# Servo12Controller.net
KiCad netlist of a schematic drawn in EAGLE
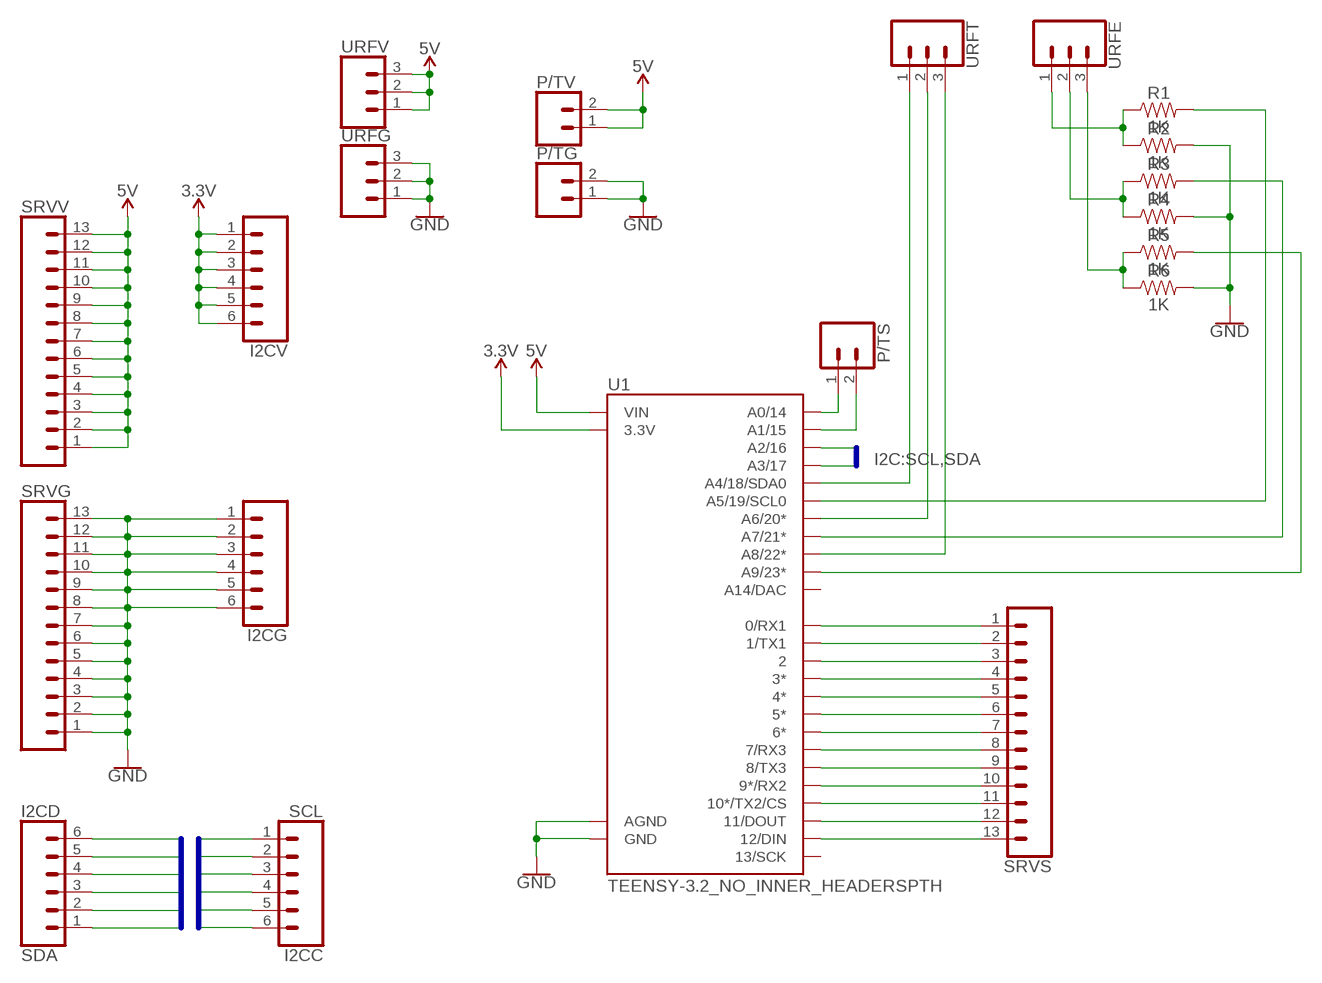
[diagram p0: schematic, sheet 1]

(export (version "E")
  (design (tool "Eeschema 10.0.6"))
  (components
    (comp (ref "I2CC")
      (value "SCL")
      (footprint "eagle-import:1X06_LOCK")
      (libsource (lib "eagle-import") (part "CONN_06LOCK"))
    )
    (comp (ref "I2CD")
      (value "SDA")
      (footprint "eagle-import:1X06_LOCK")
      (libsource (lib "eagle-import") (part "CONN_06LOCK"))
    )
    (comp (ref "I2CG")
      (value "CONN_06LOCK")
      (footprint "eagle-import:1X06_LOCK")
      (libsource (lib "eagle-import") (part "CONN_06LOCK"))
    )
    (comp (ref "I2CV")
      (value "CONN_06LOCK")
      (footprint "eagle-import:1X06_LOCK")
      (libsource (lib "eagle-import") (part "CONN_06LOCK"))
    )
    (comp (ref "P/TG")
      (value "CONN_02LOCK")
      (footprint "eagle-import:1X02_LOCK")
      (libsource (lib "eagle-import") (part "CONN_02LOCK"))
    )
    (comp (ref "P/TS")
      (value "CONN_02LOCK")
      (footprint "eagle-import:1X02_LOCK")
      (libsource (lib "eagle-import") (part "CONN_02LOCK"))
    )
    (comp (ref "P/TV")
      (value "CONN_02LOCK")
      (footprint "eagle-import:1X02_LOCK")
      (libsource (lib "eagle-import") (part "CONN_02LOCK"))
    )
    (comp (ref "R1")
      (value "1K")
      (footprint "eagle-import:AXIAL-0.3")
      (libsource (lib "eagle-import") (part "RESISTORAXIAL-0.3"))
    )
    (comp (ref "R2")
      (value "1K")
      (footprint "eagle-import:AXIAL-0.3")
      (libsource (lib "eagle-import") (part "RESISTORAXIAL-0.3"))
    )
    (comp (ref "R3")
      (value "1K")
      (footprint "eagle-import:AXIAL-0.3")
      (libsource (lib "eagle-import") (part "RESISTORAXIAL-0.3"))
    )
    (comp (ref "R4")
      (value "1K")
      (footprint "eagle-import:AXIAL-0.3")
      (libsource (lib "eagle-import") (part "RESISTORAXIAL-0.3"))
    )
    (comp (ref "R5")
      (value "1K")
      (footprint "eagle-import:AXIAL-0.3")
      (libsource (lib "eagle-import") (part "RESISTORAXIAL-0.3"))
    )
    (comp (ref "R6")
      (value "1K")
      (footprint "eagle-import:AXIAL-0.3")
      (libsource (lib "eagle-import") (part "RESISTORAXIAL-0.3"))
    )
    (comp (ref "SRVG")
      (value "CONN_13LOCK")
      (footprint "eagle-import:1X13_LOCK")
      (libsource (lib "eagle-import") (part "CONN_13LOCK"))
    )
    (comp (ref "SRVS")
      (value "CONN_13LOCK")
      (footprint "eagle-import:1X13_LOCK")
      (libsource (lib "eagle-import") (part "CONN_13LOCK"))
    )
    (comp (ref "SRVV")
      (value "CONN_13LOCK")
      (footprint "eagle-import:1X13_LOCK")
      (libsource (lib "eagle-import") (part "CONN_13LOCK"))
    )
    (comp (ref "U1")
      (value "TEENSY-3.2_NO_INNER_HEADERSPTH")
      (footprint "eagle-import:TEENSY_TEENSY-3.2-PTH")
      (libsource (lib "eagle-import") (part "TEENSY-3.2_NO_INNER_HEADERSPTH"))
    )
    (comp (ref "URFE")
      (value "CONN_03LOCK")
      (footprint "eagle-import:1X03_LOCK")
      (libsource (lib "eagle-import") (part "CONN_03LOCK"))
    )
    (comp (ref "URFG")
      (value "CONN_03LOCK")
      (footprint "eagle-import:1X03_LOCK")
      (libsource (lib "eagle-import") (part "CONN_03LOCK"))
    )
    (comp (ref "URFT")
      (value "CONN_03LOCK")
      (footprint "eagle-import:1X03_LOCK")
      (libsource (lib "eagle-import") (part "CONN_03LOCK"))
    )
    (comp (ref "URFV")
      (value "CONN_03LOCK")
      (footprint "eagle-import:1X03_LOCK")
      (libsource (lib "eagle-import") (part "CONN_03LOCK"))
    )
  )
  (nets
    (net (code "2") (name "/I2C:SCL") (class "Default")
      (node (ref "I2CC") (pin "1") (pinfunction "1_1") (pintype "passive"))
      (node (ref "I2CC") (pin "2") (pinfunction "2_2") (pintype "passive"))
      (node (ref "I2CC") (pin "3") (pinfunction "3_3") (pintype "passive"))
      (node (ref "I2CC") (pin "4") (pinfunction "4_4") (pintype "passive"))
      (node (ref "I2CC") (pin "5") (pinfunction "5_5") (pintype "passive"))
      (node (ref "I2CC") (pin "6") (pinfunction "6_6") (pintype "passive"))
      (node (ref "U1") (pin "16") (pinfunction "A2/16_16") (pintype "bidirectional"))
    )
    (net (code "3") (name "/SDA") (class "Default")
      (node (ref "I2CD") (pin "1") (pinfunction "1_1") (pintype "passive"))
      (node (ref "I2CD") (pin "2") (pinfunction "2_2") (pintype "passive"))
      (node (ref "I2CD") (pin "3") (pinfunction "3_3") (pintype "passive"))
      (node (ref "I2CD") (pin "4") (pinfunction "4_4") (pintype "passive"))
      (node (ref "I2CD") (pin "5") (pinfunction "5_5") (pintype "passive"))
      (node (ref "I2CD") (pin "6") (pinfunction "6_6") (pintype "passive"))
      (node (ref "U1") (pin "17") (pinfunction "A3/17_17") (pintype "bidirectional"))
    )
    (net (code "5") (name "3.3V") (class "Default")
      (node (ref "I2CV") (pin "1") (pinfunction "1_1") (pintype "passive"))
      (node (ref "I2CV") (pin "2") (pinfunction "2_2") (pintype "passive"))
      (node (ref "I2CV") (pin "3") (pinfunction "3_3") (pintype "passive"))
      (node (ref "I2CV") (pin "4") (pinfunction "4_4") (pintype "passive"))
      (node (ref "I2CV") (pin "5") (pinfunction "5_5") (pintype "passive"))
      (node (ref "I2CV") (pin "6") (pinfunction "6_6") (pintype "passive"))
      (node (ref "U1") (pin "3.3V") (pinfunction "3.3V_3.3V") (pintype "bidirectional"))
      (node (ref "U1") (pin "3.3V-1") (pinfunction "3.3V_3.3V-1") (pintype "bidirectional"))
    )
    (net (code "6") (name "5V") (class "Default")
      (node (ref "P/TV") (pin "1") (pinfunction "1_1") (pintype "passive"))
      (node (ref "P/TV") (pin "2") (pinfunction "2_2") (pintype "passive"))
      (node (ref "SRVV") (pin "1") (pinfunction "1_1") (pintype "passive"))
      (node (ref "SRVV") (pin "10") (pinfunction "10_10") (pintype "passive"))
      (node (ref "SRVV") (pin "11") (pinfunction "11_11") (pintype "passive"))
      (node (ref "SRVV") (pin "12") (pinfunction "12_12") (pintype "passive"))
      (node (ref "SRVV") (pin "13") (pinfunction "13_13") (pintype "passive"))
      (node (ref "SRVV") (pin "2") (pinfunction "2_2") (pintype "passive"))
      (node (ref "SRVV") (pin "3") (pinfunction "3_3") (pintype "passive"))
      (node (ref "SRVV") (pin "4") (pinfunction "4_4") (pintype "passive"))
      (node (ref "SRVV") (pin "5") (pinfunction "5_5") (pintype "passive"))
      (node (ref "SRVV") (pin "6") (pinfunction "6_6") (pintype "passive"))
      (node (ref "SRVV") (pin "7") (pinfunction "7_7") (pintype "passive"))
      (node (ref "SRVV") (pin "8") (pinfunction "8_8") (pintype "passive"))
      (node (ref "SRVV") (pin "9") (pinfunction "9_9") (pintype "passive"))
      (node (ref "U1") (pin "VIN") (pinfunction "VIN_VIN") (pintype "bidirectional"))
      (node (ref "URFV") (pin "1") (pinfunction "1_1") (pintype "passive"))
      (node (ref "URFV") (pin "2") (pinfunction "2_2") (pintype "passive"))
      (node (ref "URFV") (pin "3") (pinfunction "3_3") (pintype "passive"))
    )
    (net (code "7") (name "GND") (class "Default")
      (node (ref "I2CG") (pin "1") (pinfunction "1_1") (pintype "passive"))
      (node (ref "I2CG") (pin "2") (pinfunction "2_2") (pintype "passive"))
      (node (ref "I2CG") (pin "3") (pinfunction "3_3") (pintype "passive"))
      (node (ref "I2CG") (pin "4") (pinfunction "4_4") (pintype "passive"))
      (node (ref "I2CG") (pin "5") (pinfunction "5_5") (pintype "passive"))
      (node (ref "I2CG") (pin "6") (pinfunction "6_6") (pintype "passive"))
      (node (ref "P/TG") (pin "1") (pinfunction "1_1") (pintype "passive"))
      (node (ref "P/TG") (pin "2") (pinfunction "2_2") (pintype "passive"))
      (node (ref "R2") (pin "P$2") (pinfunction "2_P$2") (pintype "passive"))
      (node (ref "R4") (pin "P$2") (pinfunction "2_P$2") (pintype "passive"))
      (node (ref "R6") (pin "P$2") (pinfunction "2_P$2") (pintype "passive"))
      (node (ref "SRVG") (pin "1") (pinfunction "1_1") (pintype "passive"))
      (node (ref "SRVG") (pin "10") (pinfunction "10_10") (pintype "passive"))
      (node (ref "SRVG") (pin "11") (pinfunction "11_11") (pintype "passive"))
      (node (ref "SRVG") (pin "12") (pinfunction "12_12") (pintype "passive"))
      (node (ref "SRVG") (pin "13") (pinfunction "13_13") (pintype "passive"))
      (node (ref "SRVG") (pin "2") (pinfunction "2_2") (pintype "passive"))
      (node (ref "SRVG") (pin "3") (pinfunction "3_3") (pintype "passive"))
      (node (ref "SRVG") (pin "4") (pinfunction "4_4") (pintype "passive"))
      (node (ref "SRVG") (pin "5") (pinfunction "5_5") (pintype "passive"))
      (node (ref "SRVG") (pin "6") (pinfunction "6_6") (pintype "passive"))
      (node (ref "SRVG") (pin "7") (pinfunction "7_7") (pintype "passive"))
      (node (ref "SRVG") (pin "8") (pinfunction "8_8") (pintype "passive"))
      (node (ref "SRVG") (pin "9") (pinfunction "9_9") (pintype "passive"))
      (node (ref "U1") (pin "AGND") (pinfunction "AGND_AGND") (pintype "bidirectional"))
      (node (ref "U1") (pin "GND") (pinfunction "GND_GND") (pintype "bidirectional"))
      (node (ref "U1") (pin "GND1") (pinfunction "GND_GND1") (pintype "bidirectional"))
      (node (ref "URFG") (pin "1") (pinfunction "1_1") (pintype "passive"))
      (node (ref "URFG") (pin "2") (pinfunction "2_2") (pintype "passive"))
      (node (ref "URFG") (pin "3") (pinfunction "3_3") (pintype "passive"))
    )
    (net (code "8") (name "Net-(R1-1)") (class "Default")
      (node (ref "R1") (pin "P$1") (pinfunction "1_P$1") (pintype "passive"))
      (node (ref "R2") (pin "P$1") (pinfunction "1_P$1") (pintype "passive"))
      (node (ref "URFE") (pin "1") (pinfunction "1_1") (pintype "passive"))
    )
    (net (code "9") (name "Net-(R1-2)") (class "Default")
      (node (ref "R1") (pin "P$2") (pinfunction "2_P$2") (pintype "passive"))
      (node (ref "U1") (pin "19") (pinfunction "A5/19/SCL0_19") (pintype "bidirectional"))
    )
    (net (code "10") (name "Net-(R3-1)") (class "Default")
      (node (ref "R3") (pin "P$1") (pinfunction "1_P$1") (pintype "passive"))
      (node (ref "R4") (pin "P$1") (pinfunction "1_P$1") (pintype "passive"))
      (node (ref "URFE") (pin "2") (pinfunction "2_2") (pintype "passive"))
    )
    (net (code "11") (name "Net-(R3-2)") (class "Default")
      (node (ref "R3") (pin "P$2") (pinfunction "2_P$2") (pintype "passive"))
      (node (ref "U1") (pin "21") (pinfunction "A7/21*_21") (pintype "bidirectional"))
    )
    (net (code "12") (name "Net-(R5-1)") (class "Default")
      (node (ref "R5") (pin "P$1") (pinfunction "1_P$1") (pintype "passive"))
      (node (ref "R6") (pin "P$1") (pinfunction "1_P$1") (pintype "passive"))
      (node (ref "URFE") (pin "3") (pinfunction "3_3") (pintype "passive"))
    )
    (net (code "13") (name "Net-(R5-2)") (class "Default")
      (node (ref "R5") (pin "P$2") (pinfunction "2_P$2") (pintype "passive"))
      (node (ref "U1") (pin "23") (pinfunction "A9/23*_23") (pintype "bidirectional"))
    )
    (net (code "14") (name "Net-(SRVS-Pad3)") (class "Default")
      (node (ref "SRVS") (pin "3") (pinfunction "3_3") (pintype "passive"))
      (node (ref "U1") (pin "2") (pinfunction "2_2") (pintype "bidirectional"))
    )
    (net (code "15") (name "Net-(U1-0{slash}RX1)") (class "Default")
      (node (ref "SRVS") (pin "1") (pinfunction "1_1") (pintype "passive"))
      (node (ref "U1") (pin "0") (pinfunction "0/RX1_0") (pintype "bidirectional"))
    )
    (net (code "16") (name "Net-(U1-1{slash}TX1)") (class "Default")
      (node (ref "SRVS") (pin "2") (pinfunction "2_2") (pintype "passive"))
      (node (ref "U1") (pin "1") (pinfunction "1/TX1_1") (pintype "bidirectional"))
    )
    (net (code "17") (name "Net-(U1-3*)") (class "Default")
      (node (ref "SRVS") (pin "4") (pinfunction "4_4") (pintype "passive"))
      (node (ref "U1") (pin "3") (pinfunction "3*_3") (pintype "bidirectional"))
    )
    (net (code "18") (name "Net-(U1-4*)") (class "Default")
      (node (ref "SRVS") (pin "5") (pinfunction "5_5") (pintype "passive"))
      (node (ref "U1") (pin "4") (pinfunction "4*_4") (pintype "bidirectional"))
    )
    (net (code "19") (name "Net-(U1-5*)") (class "Default")
      (node (ref "SRVS") (pin "6") (pinfunction "6_6") (pintype "passive"))
      (node (ref "U1") (pin "5") (pinfunction "5*_5") (pintype "bidirectional"))
    )
    (net (code "20") (name "Net-(U1-6*)") (class "Default")
      (node (ref "SRVS") (pin "7") (pinfunction "7_7") (pintype "passive"))
      (node (ref "U1") (pin "6") (pinfunction "6*_6") (pintype "bidirectional"))
    )
    (net (code "21") (name "Net-(U1-7{slash}RX3)") (class "Default")
      (node (ref "SRVS") (pin "8") (pinfunction "8_8") (pintype "passive"))
      (node (ref "U1") (pin "7") (pinfunction "7/RX3_7") (pintype "bidirectional"))
    )
    (net (code "22") (name "Net-(U1-8{slash}TX3)") (class "Default")
      (node (ref "SRVS") (pin "9") (pinfunction "9_9") (pintype "passive"))
      (node (ref "U1") (pin "8") (pinfunction "8/TX3_8") (pintype "bidirectional"))
    )
    (net (code "23") (name "Net-(U1-9*{slash}RX2)") (class "Default")
      (node (ref "SRVS") (pin "10") (pinfunction "10_10") (pintype "passive"))
      (node (ref "U1") (pin "9") (pinfunction "9*/RX2_9") (pintype "bidirectional"))
    )
    (net (code "24") (name "Net-(U1-10*{slash}TX2{slash}CS)") (class "Default")
      (node (ref "SRVS") (pin "11") (pinfunction "11_11") (pintype "passive"))
      (node (ref "U1") (pin "10") (pinfunction "10*/TX2/CS_10") (pintype "bidirectional"))
    )
    (net (code "25") (name "Net-(U1-11{slash}DOUT)") (class "Default")
      (node (ref "SRVS") (pin "12") (pinfunction "12_12") (pintype "passive"))
      (node (ref "U1") (pin "11") (pinfunction "11/DOUT_11") (pintype "bidirectional"))
    )
    (net (code "26") (name "Net-(U1-12{slash}DIN)") (class "Default")
      (node (ref "SRVS") (pin "13") (pinfunction "13_13") (pintype "passive"))
      (node (ref "U1") (pin "12") (pinfunction "12/DIN_12") (pintype "bidirectional"))
    )
    (net (code "27") (name "Net-(U1-A0{slash}14)") (class "Default")
      (node (ref "P/TS") (pin "1") (pinfunction "1_1") (pintype "passive"))
      (node (ref "U1") (pin "14") (pinfunction "A0/14_14") (pintype "bidirectional"))
    )
    (net (code "28") (name "Net-(U1-A1{slash}15)") (class "Default")
      (node (ref "P/TS") (pin "2") (pinfunction "2_2") (pintype "passive"))
      (node (ref "U1") (pin "15") (pinfunction "A1/15_15") (pintype "bidirectional"))
    )
    (net (code "29") (name "Net-(U1-A4{slash}18{slash}SDA0)") (class "Default")
      (node (ref "U1") (pin "18") (pinfunction "A4/18/SDA0_18") (pintype "bidirectional"))
      (node (ref "URFT") (pin "1") (pinfunction "1_1") (pintype "passive"))
    )
    (net (code "30") (name "Net-(U1-A6{slash}20*)") (class "Default")
      (node (ref "U1") (pin "20") (pinfunction "A6/20*_20") (pintype "bidirectional"))
      (node (ref "URFT") (pin "2") (pinfunction "2_2") (pintype "passive"))
    )
    (net (code "31") (name "Net-(U1-A8{slash}22*)") (class "Default")
      (node (ref "U1") (pin "22") (pinfunction "A8/22*_22") (pintype "bidirectional"))
      (node (ref "URFT") (pin "3") (pinfunction "3_3") (pintype "passive"))
    )
    (net (code "32") (name "unconnected-(U1-13{slash}SCK-Pad13)") (class "Default")
      (node (ref "U1") (pin "13") (pinfunction "13/SCK_13") (pintype "bidirectional"))
    )
    (net (code "33") (name "unconnected-(U1-PadA14{slash}DAC)") (class "Default")
      (node (ref "U1") (pin "A14/DAC") (pinfunction "A14/DAC_A14/DAC") (pintype "bidirectional"))
    )
  )
)
